# GPIO.net
KiCad netlist of a schematic drawn in Altium Designer
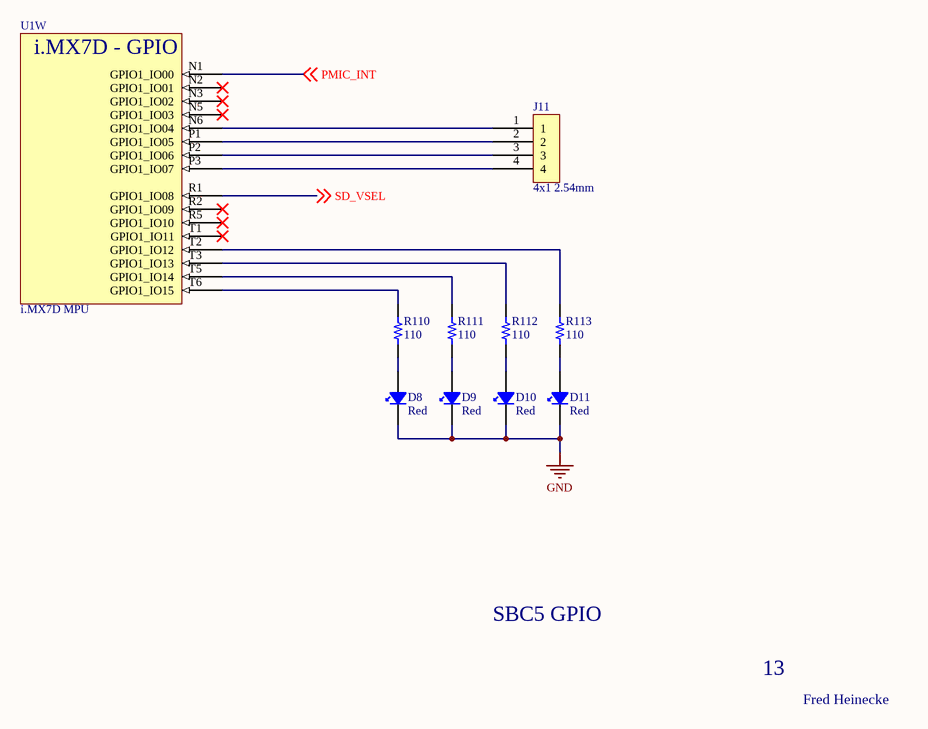
[diagram p0: GPIO.SchDoc]

(export (version "E")
  (design (tool "Eeschema 10.0.6"))
  (components
    (comp (ref "D8")
      (value "Red")
      (footprint "D0603")
      (description "WURTH ELEKTRONIK - 150060RS75000 - LED, Red, 625 nm, 2 V, 30 mA, 250 mcd RoHS Compliant: Yes")
      (fields
        (field (name "MANUFACTURER") "Wurth Electronics")
        (field (name "MANUFACTURER PART NUMBER") "150060RS75000")
      )
      (libsource (lib "SBC5") (part "150060RS75000"))
    )
    (comp (ref "D9")
      (value "Red")
      (footprint "D0603")
      (description "WURTH ELEKTRONIK - 150060RS75000 - LED, Red, 625 nm, 2 V, 30 mA, 250 mcd RoHS Compliant: Yes")
      (fields
        (field (name "MANUFACTURER") "Wurth Electronics")
        (field (name "MANUFACTURER PART NUMBER") "150060RS75000")
      )
      (libsource (lib "SBC5") (part "150060RS75000"))
    )
    (comp (ref "D10")
      (value "Red")
      (footprint "D0603")
      (description "WURTH ELEKTRONIK - 150060RS75000 - LED, Red, 625 nm, 2 V, 30 mA, 250 mcd RoHS Compliant: Yes")
      (fields
        (field (name "MANUFACTURER") "Wurth Electronics")
        (field (name "MANUFACTURER PART NUMBER") "150060RS75000")
      )
      (libsource (lib "SBC5") (part "150060RS75000"))
    )
    (comp (ref "D11")
      (value "Red")
      (footprint "D0603")
      (description "WURTH ELEKTRONIK - 150060RS75000 - LED, Red, 625 nm, 2 V, 30 mA, 250 mcd RoHS Compliant: Yes")
      (fields
        (field (name "MANUFACTURER") "Wurth Electronics")
        (field (name "MANUFACTURER PART NUMBER") "150060RS75000")
      )
      (libsource (lib "SBC5") (part "150060RS75000"))
    )
    (comp (ref "J11")
      (value "4x1 2.54mm")
      (footprint "PH1-04-UA")
      (description "Conn Unshrouded Header HDR 4 POS 2.54mm Solder ST Thru-Hole Bag")
      (fields
        (field (name "MANUFACTURER") "Adam Equipment")
        (field (name "MANUFACTURER PART NUMBER") "PH1-04-UA")
      )
      (libsource (lib "SBC5") (part "PH1-04-UA"))
    )
    (comp (ref "R110")
      (value "110")
      (footprint "R0402")
      (description "Res Thick Film 0402 110 Ohm 1% 0.063W(1/16W) ±100ppm/C Pad SMD Automotive T/R")
      (fields
        (field (name "MANUFACTURER") "Stackpole Electronics")
        (field (name "MANUFACTURER PART NUMBER") "RMCF0402FT110R")
      )
      (libsource (lib "SBC5") (part "RMCF0402FT110R"))
    )
    (comp (ref "R111")
      (value "110")
      (footprint "R0402")
      (description "Res Thick Film 0402 110 Ohm 1% 0.063W(1/16W) ±100ppm/C Pad SMD Automotive T/R")
      (fields
        (field (name "MANUFACTURER") "Stackpole Electronics")
        (field (name "MANUFACTURER PART NUMBER") "RMCF0402FT110R")
      )
      (libsource (lib "SBC5") (part "RMCF0402FT110R"))
    )
    (comp (ref "R112")
      (value "110")
      (footprint "R0402")
      (description "Res Thick Film 0402 110 Ohm 1% 0.063W(1/16W) ±100ppm/C Pad SMD Automotive T/R")
      (fields
        (field (name "MANUFACTURER") "Stackpole Electronics")
        (field (name "MANUFACTURER PART NUMBER") "RMCF0402FT110R")
      )
      (libsource (lib "SBC5") (part "RMCF0402FT110R"))
    )
    (comp (ref "R113")
      (value "110")
      (footprint "R0402")
      (description "Res Thick Film 0402 110 Ohm 1% 0.063W(1/16W) ±100ppm/C Pad SMD Automotive T/R")
      (fields
        (field (name "MANUFACTURER") "Stackpole Electronics")
        (field (name "MANUFACTURER PART NUMBER") "RMCF0402FT110R")
      )
      (libsource (lib "SBC5") (part "RMCF0402FT110R"))
    )
    (comp (ref "U1")
      (value "i.MX7D MPU")
      (footprint "BGA541C75P25X25_1900X1900X140")
      (description "Heterogeneous Multicore Processing Architecture")
      (fields
        (field (name "MANUFACTURER") "NXP Freescale")
        (field (name "MANUFACTURER PART NUMBER") "MCIMX7D2DVM12SD")
      )
      (libsource (lib "SBC5") (part "MCIMX7D2DVM12SD"))
    )
  )
  (nets
    (net (code "1") (name "GND") (class "Default")
      (node (ref "D10") (pin "K") (pinfunction "K_K") (pintype "passive"))
      (node (ref "D11") (pin "K") (pinfunction "K_K") (pintype "passive"))
      (node (ref "D8") (pin "K") (pinfunction "K_K") (pintype "passive"))
      (node (ref "D9") (pin "K") (pinfunction "K_K") (pintype "passive"))
    )
    (net (code "2") (name "Net-(D8-PadA)") (class "Default")
      (node (ref "D8") (pin "A") (pinfunction "A_A") (pintype "passive"))
      (node (ref "R110") (pin "1") (pinfunction "1_1") (pintype "passive"))
    )
    (net (code "3") (name "Net-(D9-PadA)") (class "Default")
      (node (ref "D9") (pin "A") (pinfunction "A_A") (pintype "passive"))
      (node (ref "R111") (pin "1") (pinfunction "1_1") (pintype "passive"))
    )
    (net (code "4") (name "Net-(D10-PadA)") (class "Default")
      (node (ref "D10") (pin "A") (pinfunction "A_A") (pintype "passive"))
      (node (ref "R112") (pin "1") (pinfunction "1_1") (pintype "passive"))
    )
    (net (code "5") (name "Net-(D11-PadA)") (class "Default")
      (node (ref "D11") (pin "A") (pinfunction "A_A") (pintype "passive"))
      (node (ref "R113") (pin "1") (pinfunction "1_1") (pintype "passive"))
    )
    (net (code "6") (name "Net-(U1W-GPIO1_IO04)") (class "Default")
      (node (ref "J11") (pin "1") (pinfunction "1_1") (pintype "passive"))
      (node (ref "U1") (pin "N6") (pinfunction "GPIO1_IO04_N6") (pintype "input"))
    )
    (net (code "7") (name "Net-(U1W-GPIO1_IO05)") (class "Default")
      (node (ref "J11") (pin "2") (pinfunction "2_2") (pintype "passive"))
      (node (ref "U1") (pin "P1") (pinfunction "GPIO1_IO05_P1") (pintype "input"))
    )
    (net (code "8") (name "Net-(U1W-GPIO1_IO06)") (class "Default")
      (node (ref "J11") (pin "3") (pinfunction "3_3") (pintype "passive"))
      (node (ref "U1") (pin "P2") (pinfunction "GPIO1_IO06_P2") (pintype "input"))
    )
    (net (code "9") (name "Net-(U1W-GPIO1_IO07)") (class "Default")
      (node (ref "J11") (pin "4") (pinfunction "4_4") (pintype "passive"))
      (node (ref "U1") (pin "P3") (pinfunction "GPIO1_IO07_P3") (pintype "input"))
    )
    (net (code "10") (name "Net-(U1W-GPIO1_IO12)") (class "Default")
      (node (ref "R113") (pin "2") (pinfunction "2_2") (pintype "passive"))
      (node (ref "U1") (pin "T2") (pinfunction "GPIO1_IO12_T2") (pintype "input"))
    )
    (net (code "11") (name "Net-(U1W-GPIO1_IO13)") (class "Default")
      (node (ref "R112") (pin "2") (pinfunction "2_2") (pintype "passive"))
      (node (ref "U1") (pin "T3") (pinfunction "GPIO1_IO13_T3") (pintype "input"))
    )
    (net (code "12") (name "Net-(U1W-GPIO1_IO14)") (class "Default")
      (node (ref "R111") (pin "2") (pinfunction "2_2") (pintype "passive"))
      (node (ref "U1") (pin "T5") (pinfunction "GPIO1_IO14_T5") (pintype "input"))
    )
    (net (code "13") (name "Net-(U1W-GPIO1_IO15)") (class "Default")
      (node (ref "R110") (pin "2") (pinfunction "2_2") (pintype "passive"))
      (node (ref "U1") (pin "T6") (pinfunction "GPIO1_IO15_T6") (pintype "input"))
    )
    (net (code "14") (name "PMIC_INT") (class "Default")
      (node (ref "U1") (pin "N1") (pinfunction "GPIO1_IO00_N1") (pintype "input"))
    )
    (net (code "15") (name "SD_VSEL") (class "Default")
      (node (ref "U1") (pin "R1") (pinfunction "GPIO1_IO08_R1") (pintype "input"))
    )
    (net (code "16") (name "unconnected-(U1W-GPIO1_IO01-PadN2)") (class "Default")
      (node (ref "U1") (pin "N2") (pinfunction "GPIO1_IO01_N2") (pintype "input+no_connect"))
    )
    (net (code "17") (name "unconnected-(U1W-GPIO1_IO02-PadN3)") (class "Default")
      (node (ref "U1") (pin "N3") (pinfunction "GPIO1_IO02_N3") (pintype "input+no_connect"))
    )
    (net (code "18") (name "unconnected-(U1W-GPIO1_IO03-PadN5)") (class "Default")
      (node (ref "U1") (pin "N5") (pinfunction "GPIO1_IO03_N5") (pintype "input+no_connect"))
    )
    (net (code "19") (name "unconnected-(U1W-GPIO1_IO09-PadR2)") (class "Default")
      (node (ref "U1") (pin "R2") (pinfunction "GPIO1_IO09_R2") (pintype "input+no_connect"))
    )
    (net (code "20") (name "unconnected-(U1W-GPIO1_IO10-PadR5)") (class "Default")
      (node (ref "U1") (pin "R5") (pinfunction "GPIO1_IO10_R5") (pintype "input+no_connect"))
    )
    (net (code "21") (name "unconnected-(U1W-GPIO1_IO11-PadT1)") (class "Default")
      (node (ref "U1") (pin "T1") (pinfunction "GPIO1_IO11_T1") (pintype "input+no_connect"))
    )
  )
)
